# rangkaian_skematik.net
KiCad netlist of a schematic drawn in EAGLE
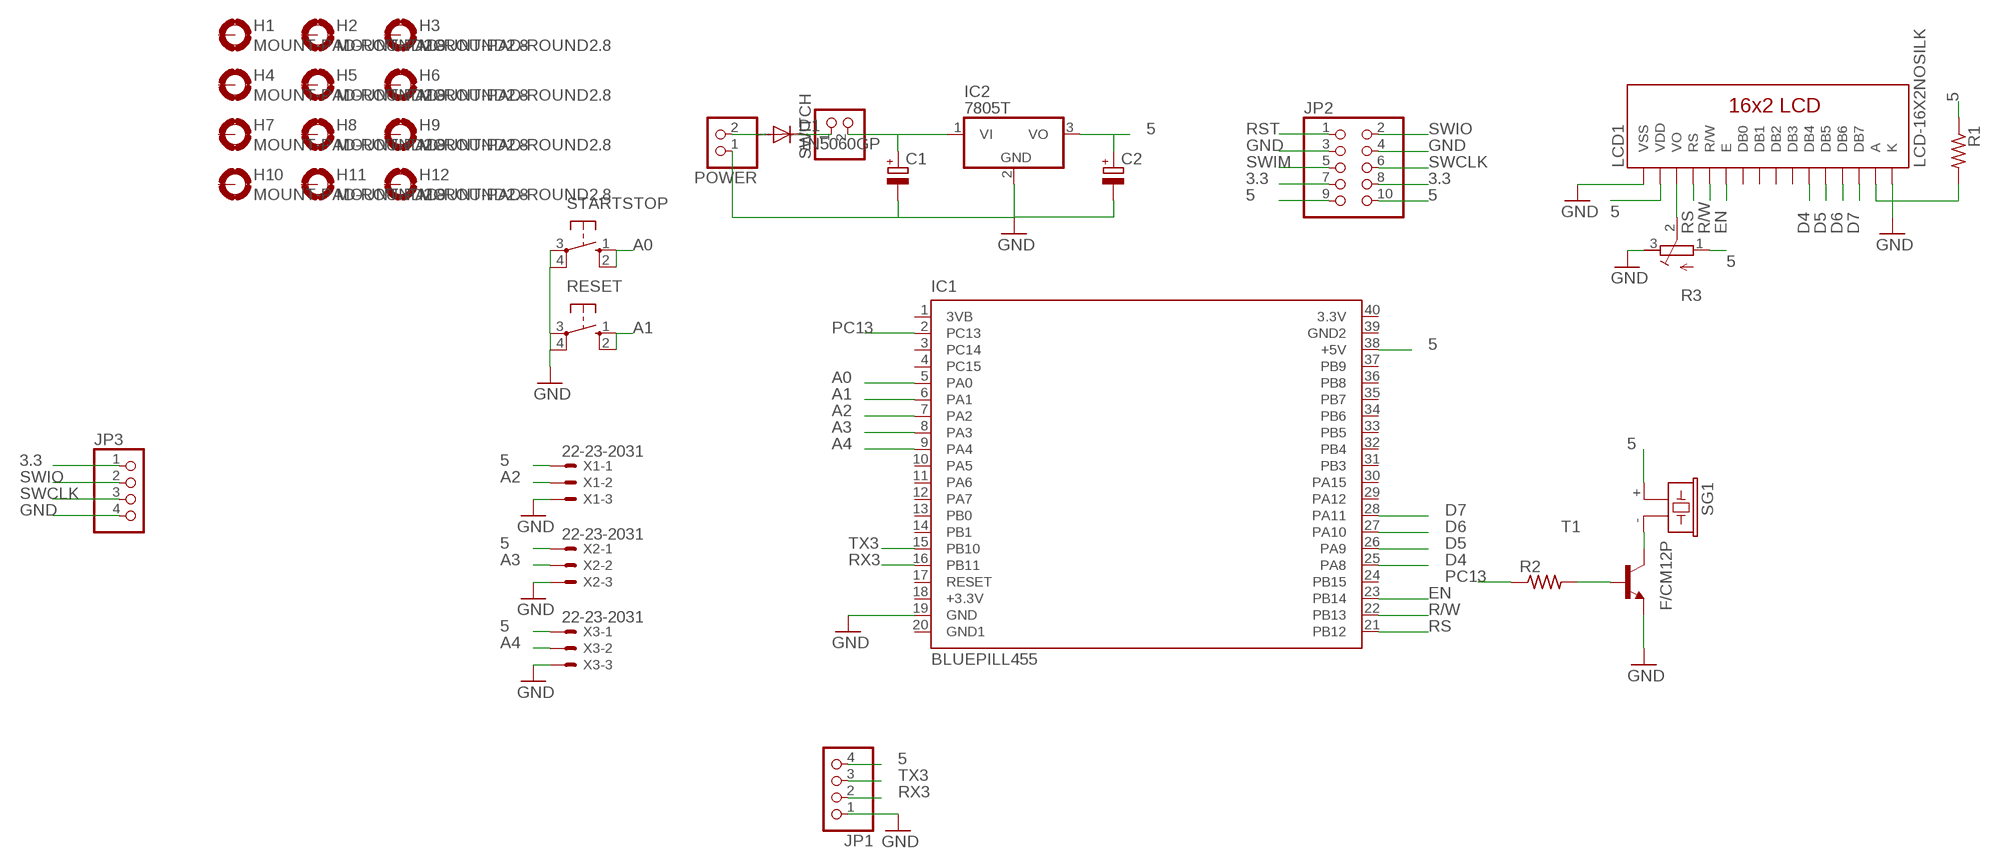
[diagram p0: schematic, sheet 1]

(export (version "E")
  (design (tool "Eeschema 10.0.6"))
  (components
    (comp (ref "C1")
      (value "CPOL-EUE2.5-7")
      (footprint "eagle-import:E2,5-7")
      (libsource (lib "eagle-import") (part "CPOL-EUE2.5-7"))
    )
    (comp (ref "C2")
      (value "CPOL-EUE2.5-6")
      (footprint "eagle-import:E2,5-6")
      (libsource (lib "eagle-import") (part "CPOL-EUE2.5-6"))
    )
    (comp (ref "D1")
      (value "1N5060GP")
      (footprint "eagle-import:DO15-12")
      (libsource (lib "eagle-import") (part "1N5060GP"))
    )
    (comp (ref "H1")
      (value "MOUNT-PAD-ROUND2.8")
      (footprint "eagle-import:2,8-PAD")
      (libsource (lib "eagle-import") (part "MOUNT-PAD-ROUND2.8"))
    )
    (comp (ref "H2")
      (value "MOUNT-PAD-ROUND2.8")
      (footprint "eagle-import:2,8-PAD")
      (libsource (lib "eagle-import") (part "MOUNT-PAD-ROUND2.8"))
    )
    (comp (ref "H3")
      (value "MOUNT-PAD-ROUND2.8")
      (footprint "eagle-import:2,8-PAD")
      (libsource (lib "eagle-import") (part "MOUNT-PAD-ROUND2.8"))
    )
    (comp (ref "H4")
      (value "MOUNT-PAD-ROUND2.8")
      (footprint "eagle-import:2,8-PAD")
      (libsource (lib "eagle-import") (part "MOUNT-PAD-ROUND2.8"))
    )
    (comp (ref "H5")
      (value "MOUNT-PAD-ROUND2.8")
      (footprint "eagle-import:2,8-PAD")
      (libsource (lib "eagle-import") (part "MOUNT-PAD-ROUND2.8"))
    )
    (comp (ref "H6")
      (value "MOUNT-PAD-ROUND2.8")
      (footprint "eagle-import:2,8-PAD")
      (libsource (lib "eagle-import") (part "MOUNT-PAD-ROUND2.8"))
    )
    (comp (ref "H7")
      (value "MOUNT-PAD-ROUND2.8")
      (footprint "eagle-import:2,8-PAD")
      (libsource (lib "eagle-import") (part "MOUNT-PAD-ROUND2.8"))
    )
    (comp (ref "H8")
      (value "MOUNT-PAD-ROUND2.8")
      (footprint "eagle-import:2,8-PAD")
      (libsource (lib "eagle-import") (part "MOUNT-PAD-ROUND2.8"))
    )
    (comp (ref "H9")
      (value "MOUNT-PAD-ROUND2.8")
      (footprint "eagle-import:2,8-PAD")
      (libsource (lib "eagle-import") (part "MOUNT-PAD-ROUND2.8"))
    )
    (comp (ref "H10")
      (value "MOUNT-PAD-ROUND2.8")
      (footprint "eagle-import:2,8-PAD")
      (libsource (lib "eagle-import") (part "MOUNT-PAD-ROUND2.8"))
    )
    (comp (ref "H11")
      (value "MOUNT-PAD-ROUND2.8")
      (footprint "eagle-import:2,8-PAD")
      (libsource (lib "eagle-import") (part "MOUNT-PAD-ROUND2.8"))
    )
    (comp (ref "H12")
      (value "MOUNT-PAD-ROUND2.8")
      (footprint "eagle-import:2,8-PAD")
      (libsource (lib "eagle-import") (part "MOUNT-PAD-ROUND2.8"))
    )
    (comp (ref "IC1")
      (value "BLUEPILL455")
      (footprint "eagle-import:DIL40")
      (fields (field (name "MF") "BluePill"))
      (libsource (lib "eagle-import") (part "BLUEPILL455"))
    )
    (comp (ref "IC2")
      (value "7805T")
      (footprint "eagle-import:TO220H")
      (libsource (lib "eagle-import") (part "78T05"))
    )
    (comp (ref "JP1")
      (value "PINHD-1X4")
      (footprint "eagle-import:1X04")
      (libsource (lib "eagle-import") (part "PINHD-1X4"))
    )
    (comp (ref "JP2")
      (value "PINHD-2X5")
      (footprint "eagle-import:2X05")
      (libsource (lib "eagle-import") (part "PINHD-2X5"))
    )
    (comp (ref "JP3")
      (value "PINHD-1X4")
      (footprint "eagle-import:1X04")
      (libsource (lib "eagle-import") (part "PINHD-1X4"))
    )
    (comp (ref "LCD1")
      (value "LCD-16X2NOSILK")
      (footprint "eagle-import:LCD-16X2_NOSILK")
      (libsource (lib "eagle-import") (part "LCD-16X2NOSILK"))
    )
    (comp (ref "POWER")
      (value "PINHD-1X2")
      (footprint "eagle-import:1X02")
      (libsource (lib "eagle-import") (part "PINHD-1X2"))
    )
    (comp (ref "R1")
      (value "R-US_0207/10")
      (footprint "eagle-import:0207_10")
      (libsource (lib "eagle-import") (part "R-US_0207/10"))
    )
    (comp (ref "R2")
      (value "R-US_M0805")
      (footprint "eagle-import:M0805")
      (libsource (lib "eagle-import") (part "R-US_M0805"))
    )
    (comp (ref "R3")
      (value "R-TRIMM3339P")
      (footprint "eagle-import:RTRIM3339P")
      (libsource (lib "eagle-import") (part "R-TRIMM3339P"))
    )
    (comp (ref "RESET")
      (value "40-XX")
      (footprint "eagle-import:B3F-40XX")
      (fields (field (name "MF") "OMRON COMPONENTS USA") (field (name "MPN") "B3F-4000"))
      (libsource (lib "eagle-import") (part "40-XX"))
    )
    (comp (ref "SG1")
      (value "F/CM12P")
      (footprint "eagle-import:F_CM12P")
      (libsource (lib "eagle-import") (part "F/CM12P"))
    )
    (comp (ref "STARTSTOP")
      (value "40-XX")
      (footprint "eagle-import:B3F-40XX")
      (fields (field (name "MF") "OMRON COMPONENTS USA") (field (name "MPN") "B3F-4000"))
      (libsource (lib "eagle-import") (part "40-XX"))
    )
    (comp (ref "SWITCH")
      (value "PINHD-1X2")
      (footprint "eagle-import:1X02")
      (libsource (lib "eagle-import") (part "PINHD-1X2"))
    )
    (comp (ref "T1")
      (value "BF820-NPN-SOT23-BEC")
      (footprint "eagle-import:SOT23-BEC")
      (libsource (lib "eagle-import") (part "-NPN-SOT23-BECBF820"))
    )
    (comp (ref "X1")
      (value "22-23-2031")
      (footprint "eagle-import:22-23-2031")
      (fields (field (name "MF") "MOLEX"))
      (libsource (lib "eagle-import") (part "22-23-2031"))
    )
    (comp (ref "X2")
      (value "22-23-2031")
      (footprint "eagle-import:22-23-2031")
      (fields (field (name "MF") "MOLEX"))
      (libsource (lib "eagle-import") (part "22-23-2031"))
    )
    (comp (ref "X3")
      (value "22-23-2031")
      (footprint "eagle-import:22-23-2031")
      (fields (field (name "MF") "MOLEX"))
      (libsource (lib "eagle-import") (part "22-23-2031"))
    )
  )
  (nets
    (net (code "1") (name "/3.3") (class "Default")
      (node (ref "JP2") (pin "7") (pinfunction "7_7") (pintype "passive"))
      (node (ref "JP2") (pin "8") (pinfunction "8_8") (pintype "passive"))
      (node (ref "JP3") (pin "1") (pinfunction "1_1") (pintype "passive"))
    )
    (net (code "2") (name "/5") (class "Default")
      (node (ref "C2") (pin "+") (pinfunction "+_+") (pintype "passive"))
      (node (ref "IC1") (pin "38") (pinfunction "+5V_38") (pintype "bidirectional"))
      (node (ref "IC2") (pin "3") (pinfunction "VO_3") (pintype "passive"))
      (node (ref "JP1") (pin "4") (pinfunction "4_4") (pintype "passive"))
      (node (ref "JP2") (pin "10") (pinfunction "10_10") (pintype "passive"))
      (node (ref "JP2") (pin "9") (pinfunction "9_9") (pintype "passive"))
      (node (ref "LCD1") (pin "2") (pinfunction "VDD_2") (pintype "power_in"))
      (node (ref "R1") (pin "1") (pinfunction "1_1") (pintype "passive"))
      (node (ref "R3") (pin "1") (pinfunction "A_1") (pintype "passive"))
      (node (ref "SG1") (pin "+") (pinfunction "1_+") (pintype "passive"))
      (node (ref "X1") (pin "1") (pinfunction "S_1") (pintype "passive"))
      (node (ref "X2") (pin "1") (pinfunction "S_1") (pintype "passive"))
      (node (ref "X3") (pin "1") (pinfunction "S_1") (pintype "passive"))
    )
    (net (code "3") (name "/A0") (class "Default")
      (node (ref "IC1") (pin "5") (pinfunction "PA0_5") (pintype "bidirectional"))
      (node (ref "STARTSTOP") (pin "1") (pinfunction "S_1") (pintype "passive"))
      (node (ref "STARTSTOP") (pin "2") (pinfunction "S1_2") (pintype "passive"))
    )
    (net (code "4") (name "/A1") (class "Default")
      (node (ref "IC1") (pin "6") (pinfunction "PA1_6") (pintype "bidirectional"))
      (node (ref "RESET") (pin "1") (pinfunction "S_1") (pintype "passive"))
      (node (ref "RESET") (pin "2") (pinfunction "S1_2") (pintype "passive"))
    )
    (net (code "5") (name "/A2") (class "Default")
      (node (ref "IC1") (pin "7") (pinfunction "PA2_7") (pintype "bidirectional"))
      (node (ref "X1") (pin "2") (pinfunction "S_2") (pintype "passive"))
    )
    (net (code "6") (name "/A3") (class "Default")
      (node (ref "IC1") (pin "8") (pinfunction "PA3_8") (pintype "bidirectional"))
      (node (ref "X2") (pin "2") (pinfunction "S_2") (pintype "passive"))
    )
    (net (code "7") (name "/A4") (class "Default")
      (node (ref "IC1") (pin "9") (pinfunction "PA4_9") (pintype "bidirectional"))
      (node (ref "X3") (pin "2") (pinfunction "S_2") (pintype "passive"))
    )
    (net (code "8") (name "/D4") (class "Default")
      (node (ref "IC1") (pin "25") (pinfunction "PA8_25") (pintype "bidirectional"))
      (node (ref "LCD1") (pin "11") (pinfunction "DB4_11") (pintype "bidirectional"))
    )
    (net (code "9") (name "/D5") (class "Default")
      (node (ref "IC1") (pin "26") (pinfunction "PA9_26") (pintype "bidirectional"))
      (node (ref "LCD1") (pin "12") (pinfunction "DB5_12") (pintype "bidirectional"))
    )
    (net (code "10") (name "/D6") (class "Default")
      (node (ref "IC1") (pin "27") (pinfunction "PA10_27") (pintype "bidirectional"))
      (node (ref "LCD1") (pin "13") (pinfunction "DB6_13") (pintype "bidirectional"))
    )
    (net (code "11") (name "/D7") (class "Default")
      (node (ref "IC1") (pin "28") (pinfunction "PA11_28") (pintype "bidirectional"))
      (node (ref "LCD1") (pin "14") (pinfunction "DB7_14") (pintype "bidirectional"))
    )
    (net (code "12") (name "/EN") (class "Default")
      (node (ref "IC1") (pin "23") (pinfunction "PB14_23") (pintype "bidirectional"))
      (node (ref "LCD1") (pin "6") (pinfunction "E_6") (pintype "input"))
    )
    (net (code "13") (name "/PA6") (class "Default")
      (node (ref "IC1") (pin "11") (pinfunction "PA6_11") (pintype "power_in"))
    )
    (net (code "14") (name "/PA7") (class "Default")
      (node (ref "IC1") (pin "12") (pinfunction "PA7_12") (pintype "power_in"))
    )
    (net (code "15") (name "/PB3") (class "Default")
      (node (ref "IC1") (pin "31") (pinfunction "PB3_31") (pintype "power_in"))
    )
    (net (code "16") (name "/PB4") (class "Default")
      (node (ref "IC1") (pin "32") (pinfunction "PB4_32") (pintype "power_in"))
    )
    (net (code "17") (name "/PC13") (class "Default")
      (node (ref "IC1") (pin "2") (pinfunction "PC13_2") (pintype "bidirectional"))
      (node (ref "R2") (pin "1") (pinfunction "1_1") (pintype "passive"))
    )
    (net (code "18") (name "/RS") (class "Default")
      (node (ref "IC1") (pin "21") (pinfunction "PB12_21") (pintype "bidirectional"))
      (node (ref "LCD1") (pin "4") (pinfunction "RS_4") (pintype "input"))
    )
    (net (code "19") (name "/RST") (class "Default")
      (node (ref "JP2") (pin "1") (pinfunction "1_1") (pintype "passive"))
    )
    (net (code "20") (name "/RX3") (class "Default")
      (node (ref "IC1") (pin "16") (pinfunction "PB11_16") (pintype "bidirectional"))
      (node (ref "JP1") (pin "2") (pinfunction "2_2") (pintype "passive"))
    )
    (net (code "21") (name "/R{slash}W") (class "Default")
      (node (ref "IC1") (pin "22") (pinfunction "PB13_22") (pintype "bidirectional"))
      (node (ref "LCD1") (pin "5") (pinfunction "R/W_5") (pintype "input"))
    )
    (net (code "22") (name "/SWCLK") (class "Default")
      (node (ref "JP2") (pin "6") (pinfunction "6_6") (pintype "passive"))
      (node (ref "JP3") (pin "3") (pinfunction "3_3") (pintype "passive"))
    )
    (net (code "23") (name "/SWIM") (class "Default")
      (node (ref "JP2") (pin "5") (pinfunction "5_5") (pintype "passive"))
    )
    (net (code "24") (name "/SWIO") (class "Default")
      (node (ref "JP2") (pin "2") (pinfunction "2_2") (pintype "passive"))
      (node (ref "JP3") (pin "2") (pinfunction "2_2") (pintype "passive"))
    )
    (net (code "25") (name "/TX3") (class "Default")
      (node (ref "IC1") (pin "15") (pinfunction "PB10_15") (pintype "bidirectional"))
      (node (ref "JP1") (pin "3") (pinfunction "3_3") (pintype "passive"))
    )
    (net (code "26") (name "GND") (class "Default")
      (node (ref "C1") (pin "-") (pinfunction "-_-") (pintype "passive"))
      (node (ref "C2") (pin "-") (pinfunction "-_-") (pintype "passive"))
      (node (ref "IC1") (pin "19") (pinfunction "GND_19") (pintype "bidirectional"))
      (node (ref "IC2") (pin "2") (pinfunction "GND_2") (pintype "passive"))
      (node (ref "JP1") (pin "1") (pinfunction "1_1") (pintype "passive"))
      (node (ref "JP2") (pin "3") (pinfunction "3_3") (pintype "passive"))
      (node (ref "JP2") (pin "4") (pinfunction "4_4") (pintype "passive"))
      (node (ref "JP3") (pin "4") (pinfunction "4_4") (pintype "passive"))
      (node (ref "LCD1") (pin "1") (pinfunction "VSS_1") (pintype "power_in"))
      (node (ref "LCD1") (pin "16") (pinfunction "K_16") (pintype "power_in"))
      (node (ref "POWER") (pin "1") (pinfunction "1_1") (pintype "passive"))
      (node (ref "R3") (pin "3") (pinfunction "E_3") (pintype "passive"))
      (node (ref "RESET") (pin "3") (pinfunction "P_3") (pintype "passive"))
      (node (ref "RESET") (pin "4") (pinfunction "P1_4") (pintype "passive"))
      (node (ref "STARTSTOP") (pin "3") (pinfunction "P_3") (pintype "passive"))
      (node (ref "STARTSTOP") (pin "4") (pinfunction "P1_4") (pintype "passive"))
      (node (ref "T1") (pin "E") (pinfunction "E_E") (pintype "passive"))
      (node (ref "X1") (pin "3") (pinfunction "S_3") (pintype "passive"))
      (node (ref "X2") (pin "3") (pinfunction "S_3") (pintype "passive"))
      (node (ref "X3") (pin "3") (pinfunction "S_3") (pintype "passive"))
    )
    (net (code "27") (name "Net-(D1-PadA)") (class "Default")
      (node (ref "D1") (pin "A") (pinfunction "A_A") (pintype "passive"))
      (node (ref "POWER") (pin "2") (pinfunction "2_2") (pintype "passive"))
    )
    (net (code "28") (name "Net-(D1-PadC)") (class "Default")
      (node (ref "D1") (pin "C") (pinfunction "C_C") (pintype "passive"))
      (node (ref "SWITCH") (pin "1") (pinfunction "1_1") (pintype "passive"))
    )
    (net (code "29") (name "Net-(IC2-VI)") (class "Default")
      (node (ref "C1") (pin "+") (pinfunction "+_+") (pintype "passive"))
      (node (ref "IC2") (pin "1") (pinfunction "VI_1") (pintype "input"))
      (node (ref "SWITCH") (pin "2") (pinfunction "2_2") (pintype "passive"))
    )
    (net (code "30") (name "Net-(LCD1-A)") (class "Default")
      (node (ref "LCD1") (pin "15") (pinfunction "A_15") (pintype "power_in"))
      (node (ref "R1") (pin "2") (pinfunction "2_2") (pintype "passive"))
    )
    (net (code "31") (name "Net-(LCD1-VO)") (class "Default")
      (node (ref "LCD1") (pin "3") (pinfunction "VO_3") (pintype "bidirectional"))
      (node (ref "R3") (pin "2") (pinfunction "S_2") (pintype "passive"))
    )
    (net (code "32") (name "Net-(R2-Pad2)") (class "Default")
      (node (ref "R2") (pin "2") (pinfunction "2_2") (pintype "passive"))
      (node (ref "T1") (pin "B") (pinfunction "B_B") (pintype "passive"))
    )
    (net (code "33") (name "Net-(SG1-2)") (class "Default")
      (node (ref "SG1") (pin "-") (pinfunction "2_-") (pintype "passive"))
      (node (ref "T1") (pin "C") (pinfunction "C_C") (pintype "passive"))
    )
    (net (code "34") (name "unconnected-(H1-MOUNT-PadB2,8)") (class "Default")
      (node (ref "H1") (pin "B2,8") (pinfunction "MOUNT_B2,8") (pintype "passive"))
    )
    (net (code "35") (name "unconnected-(H2-MOUNT-PadB2,8)") (class "Default")
      (node (ref "H2") (pin "B2,8") (pinfunction "MOUNT_B2,8") (pintype "passive"))
    )
    (net (code "36") (name "unconnected-(H3-MOUNT-PadB2,8)") (class "Default")
      (node (ref "H3") (pin "B2,8") (pinfunction "MOUNT_B2,8") (pintype "passive"))
    )
    (net (code "37") (name "unconnected-(H4-MOUNT-PadB2,8)") (class "Default")
      (node (ref "H4") (pin "B2,8") (pinfunction "MOUNT_B2,8") (pintype "passive"))
    )
    (net (code "38") (name "unconnected-(H5-MOUNT-PadB2,8)") (class "Default")
      (node (ref "H5") (pin "B2,8") (pinfunction "MOUNT_B2,8") (pintype "passive"))
    )
    (net (code "39") (name "unconnected-(H6-MOUNT-PadB2,8)") (class "Default")
      (node (ref "H6") (pin "B2,8") (pinfunction "MOUNT_B2,8") (pintype "passive"))
    )
    (net (code "40") (name "unconnected-(H7-MOUNT-PadB2,8)") (class "Default")
      (node (ref "H7") (pin "B2,8") (pinfunction "MOUNT_B2,8") (pintype "passive"))
    )
    (net (code "41") (name "unconnected-(H8-MOUNT-PadB2,8)") (class "Default")
      (node (ref "H8") (pin "B2,8") (pinfunction "MOUNT_B2,8") (pintype "passive"))
    )
    (net (code "42") (name "unconnected-(H9-MOUNT-PadB2,8)") (class "Default")
      (node (ref "H9") (pin "B2,8") (pinfunction "MOUNT_B2,8") (pintype "passive"))
    )
    (net (code "43") (name "unconnected-(H10-MOUNT-PadB2,8)") (class "Default")
      (node (ref "H10") (pin "B2,8") (pinfunction "MOUNT_B2,8") (pintype "passive"))
    )
    (net (code "44") (name "unconnected-(H11-MOUNT-PadB2,8)") (class "Default")
      (node (ref "H11") (pin "B2,8") (pinfunction "MOUNT_B2,8") (pintype "passive"))
    )
    (net (code "45") (name "unconnected-(H12-MOUNT-PadB2,8)") (class "Default")
      (node (ref "H12") (pin "B2,8") (pinfunction "MOUNT_B2,8") (pintype "passive"))
    )
    (net (code "46") (name "unconnected-(IC1-+3.3V-Pad18)") (class "Default")
      (node (ref "IC1") (pin "18") (pinfunction "+3.3V_18") (pintype "bidirectional"))
    )
    (net (code "47") (name "unconnected-(IC1-3.3V-Pad40)") (class "Default")
      (node (ref "IC1") (pin "40") (pinfunction "3.3V_40") (pintype "bidirectional"))
    )
    (net (code "48") (name "unconnected-(IC1-3VB-Pad1)") (class "Default")
      (node (ref "IC1") (pin "1") (pinfunction "3VB_1") (pintype "input"))
    )
    (net (code "49") (name "unconnected-(IC1-GND1-Pad20)") (class "Default")
      (node (ref "IC1") (pin "20") (pinfunction "GND1_20") (pintype "bidirectional"))
    )
    (net (code "50") (name "unconnected-(IC1-GND2-Pad39)") (class "Default")
      (node (ref "IC1") (pin "39") (pinfunction "GND2_39") (pintype "bidirectional"))
    )
    (net (code "51") (name "unconnected-(IC1-PA5-Pad10)") (class "Default")
      (node (ref "IC1") (pin "10") (pinfunction "PA5_10") (pintype "bidirectional"))
    )
    (net (code "52") (name "unconnected-(IC1-PA12-Pad29)") (class "Default")
      (node (ref "IC1") (pin "29") (pinfunction "PA12_29") (pintype "bidirectional"))
    )
    (net (code "53") (name "unconnected-(IC1-PA15-Pad30)") (class "Default")
      (node (ref "IC1") (pin "30") (pinfunction "PA15_30") (pintype "bidirectional"))
    )
    (net (code "54") (name "unconnected-(IC1-PB0-Pad13)") (class "Default")
      (node (ref "IC1") (pin "13") (pinfunction "PB0_13") (pintype "input"))
    )
    (net (code "55") (name "unconnected-(IC1-PB1-Pad14)") (class "Default")
      (node (ref "IC1") (pin "14") (pinfunction "PB1_14") (pintype "output"))
    )
    (net (code "56") (name "unconnected-(IC1-PB5-Pad33)") (class "Default")
      (node (ref "IC1") (pin "33") (pinfunction "PB5_33") (pintype "bidirectional"))
    )
    (net (code "57") (name "unconnected-(IC1-PB6-Pad34)") (class "Default")
      (node (ref "IC1") (pin "34") (pinfunction "PB6_34") (pintype "bidirectional"))
    )
    (net (code "58") (name "unconnected-(IC1-PB7-Pad35)") (class "Default")
      (node (ref "IC1") (pin "35") (pinfunction "PB7_35") (pintype "bidirectional"))
    )
    (net (code "59") (name "unconnected-(IC1-PB8-Pad36)") (class "Default")
      (node (ref "IC1") (pin "36") (pinfunction "PB8_36") (pintype "bidirectional"))
    )
    (net (code "60") (name "unconnected-(IC1-PB9-Pad37)") (class "Default")
      (node (ref "IC1") (pin "37") (pinfunction "PB9_37") (pintype "bidirectional"))
    )
    (net (code "61") (name "unconnected-(IC1-PB15-Pad24)") (class "Default")
      (node (ref "IC1") (pin "24") (pinfunction "PB15_24") (pintype "bidirectional"))
    )
    (net (code "62") (name "unconnected-(IC1-PC14-Pad3)") (class "Default")
      (node (ref "IC1") (pin "3") (pinfunction "PC14_3") (pintype "bidirectional"))
    )
    (net (code "63") (name "unconnected-(IC1-PC15-Pad4)") (class "Default")
      (node (ref "IC1") (pin "4") (pinfunction "PC15_4") (pintype "bidirectional"))
    )
    (net (code "64") (name "unconnected-(IC1-RESET-Pad17)") (class "Default")
      (node (ref "IC1") (pin "17") (pinfunction "RESET_17") (pintype "bidirectional"))
    )
    (net (code "65") (name "unconnected-(LCD1-DB0-Pad7)") (class "Default")
      (node (ref "LCD1") (pin "7") (pinfunction "DB0_7") (pintype "bidirectional"))
    )
    (net (code "66") (name "unconnected-(LCD1-DB1-Pad8)") (class "Default")
      (node (ref "LCD1") (pin "8") (pinfunction "DB1_8") (pintype "bidirectional"))
    )
    (net (code "67") (name "unconnected-(LCD1-DB2-Pad9)") (class "Default")
      (node (ref "LCD1") (pin "9") (pinfunction "DB2_9") (pintype "bidirectional"))
    )
    (net (code "68") (name "unconnected-(LCD1-DB3-Pad10)") (class "Default")
      (node (ref "LCD1") (pin "10") (pinfunction "DB3_10") (pintype "bidirectional"))
    )
  )
)
